# xbee_remote.net
KiCad netlist of a schematic drawn in EAGLE
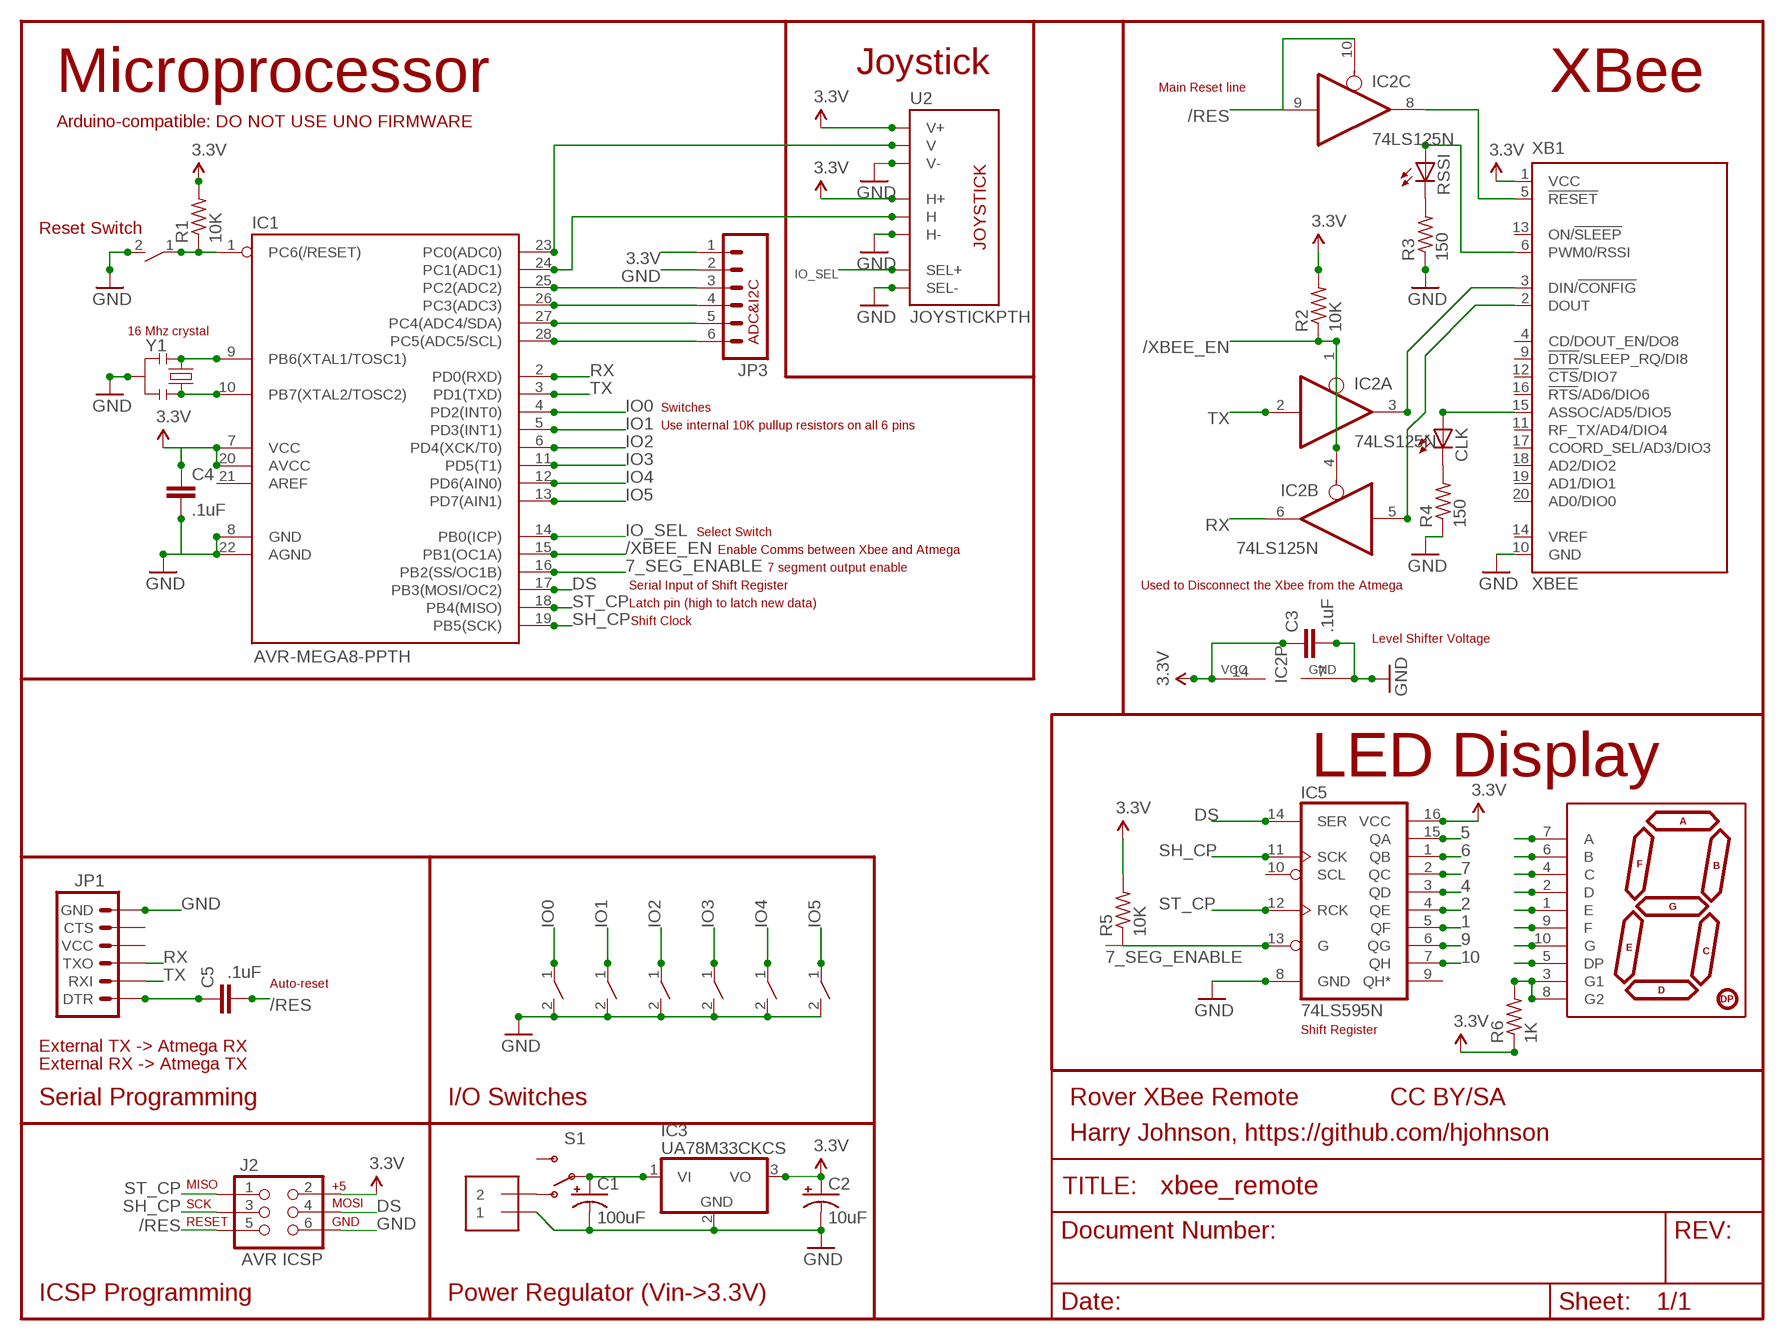
[diagram p0: schematic, sheet 1]

(export (version "E")
  (design (tool "Eeschema 10.0.6"))
  (components
    (comp (ref "C1")
      (value "100uF")
      (footprint "eagle-import:CPOL-RADIAL-100UF-25V")
      (libsource (lib "eagle-import") (part "CAP_POLPTH1"))
    )
    (comp (ref "C2")
      (value "10uF")
      (footprint "eagle-import:CPOL-RADIAL-10UF-25V")
      (libsource (lib "eagle-import") (part "CAP_POLPTH2"))
    )
    (comp (ref "C3")
      (value ".1uF")
      (footprint "eagle-import:CAP-PTH-SMALL2")
      (libsource (lib "eagle-import") (part "CAPPTH2"))
    )
    (comp (ref "C4")
      (value ".1uF")
      (footprint "eagle-import:CAP-PTH-SMALL2")
      (libsource (lib "eagle-import") (part "CAPPTH2"))
    )
    (comp (ref "C5")
      (value ".1uF")
      (footprint "eagle-import:CAP-PTH-SMALL2")
      (libsource (lib "eagle-import") (part "CAPPTH2"))
    )
    (comp (ref "CLK")
      (value "LED3MM")
      (footprint "eagle-import:LED3MM")
      (libsource (lib "eagle-import") (part "LED3MM"))
    )
    (comp (ref "IC1")
      (value "AVR-MEGA8-PPTH")
      (footprint "eagle-import:DIL28-3")
      (libsource (lib "eagle-import") (part "AVR-MEGA8-PPTH"))
    )
    (comp (ref "IC2")
      (value "74LS125N")
      (footprint "eagle-import:DIL14")
      (libsource (lib "eagle-import") (part "74125NLS"))
    )
    (comp (ref "IC3")
      (value "UA78M33CKCS")
      (footprint "eagle-import:TO220V")
      (libsource (lib "eagle-import") (part "78TV6"))
    )
    (comp (ref "IC5")
      (value "74LS595N")
      (footprint "eagle-import:DIL16")
      (libsource (lib "eagle-import") (part "74595NLS"))
    )
    (comp (ref "J1")
      (value "1X2-3.5MM")
      (footprint "eagle-import:3.5MMTERM")
      (libsource (lib "eagle-import") (part "1X2-3.5MM"))
    )
    (comp (ref "J2")
      (value "AVR ICSP")
      (footprint "eagle-import:2X3")
      (libsource (lib "eagle-import") (part "AVR_SPI_PRG_6PTH"))
    )
    (comp (ref "JP1")
      (value "ARDUINO_SERIAL_PROGRAMPTH")
      (footprint "eagle-import:1X06")
      (libsource (lib "eagle-import") (part "ARDUINO_SERIAL_PROGRAMPTH"))
    )
    (comp (ref "JP3")
      (value "M06SIP")
      (footprint "eagle-import:1X06")
      (libsource (lib "eagle-import") (part "M06SIP"))
    )
    (comp (ref "R1")
      (value "10K")
      (footprint "eagle-import:0207_10")
      (libsource (lib "eagle-import") (part "R-US_0207/10"))
    )
    (comp (ref "R2")
      (value "10K")
      (footprint "eagle-import:0207_10")
      (libsource (lib "eagle-import") (part "R-US_0207/10"))
    )
    (comp (ref "R3")
      (value "150")
      (footprint "eagle-import:0207_10")
      (libsource (lib "eagle-import") (part "R-US_0207/10"))
    )
    (comp (ref "R4")
      (value "150")
      (footprint "eagle-import:0207_10")
      (libsource (lib "eagle-import") (part "R-US_0207/10"))
    )
    (comp (ref "R5")
      (value "10K")
      (footprint "eagle-import:0207_10")
      (libsource (lib "eagle-import") (part "R-US_0207/10"))
    )
    (comp (ref "R6")
      (value "1K")
      (footprint "eagle-import:0207_10")
      (libsource (lib "eagle-import") (part "R-US_0207/10"))
    )
    (comp (ref "RSSI")
      (value "LED3MM")
      (footprint "eagle-import:LED3MM")
      (libsource (lib "eagle-import") (part "LED3MM"))
    )
    (comp (ref "S1")
      (value "SWITCH-SPSTPTH")
      (footprint "eagle-import:SWITCH-SPDT")
      (libsource (lib "eagle-import") (part "SWITCH-SPSTPTH"))
    )
    (comp (ref "U$4")
      (value "7-SEGMENT-DISPLAY-1\"-RED")
      (footprint "eagle-import:7-SEGMENT-1_PTH")
      (libsource (lib "eagle-import") (part "7-SEGMENT-DISPLAY-1{dblquote}-RED"))
    )
    (comp (ref "U$8")
      (value "TACT_TL1107")
      (footprint "eagle-import:TACT_TL1107")
      (libsource (lib "eagle-import") (part "TACT_TL1107"))
    )
    (comp (ref "U$9")
      (value "TACT_TL1107")
      (footprint "eagle-import:TACT_TL1107")
      (libsource (lib "eagle-import") (part "TACT_TL1107"))
    )
    (comp (ref "U$10")
      (value "TACT_TL1107")
      (footprint "eagle-import:TACT_TL1107")
      (libsource (lib "eagle-import") (part "TACT_TL1107"))
    )
    (comp (ref "U$11")
      (value "TACT_TL1107")
      (footprint "eagle-import:TACT_TL1107")
      (libsource (lib "eagle-import") (part "TACT_TL1107"))
    )
    (comp (ref "U$12")
      (value "TACT_TL1107")
      (footprint "eagle-import:TACT_TL1107")
      (libsource (lib "eagle-import") (part "TACT_TL1107"))
    )
    (comp (ref "U$13")
      (value "TACT_TL1107")
      (footprint "eagle-import:TACT_TL1107")
      (libsource (lib "eagle-import") (part "TACT_TL1107"))
    )
    (comp (ref "U$14")
      (value "TACT_TL1107")
      (footprint "eagle-import:TACT_TL1107")
      (libsource (lib "eagle-import") (part "TACT_TL1107"))
    )
    (comp (ref "U2")
      (value "JOYSTICKPTH")
      (footprint "eagle-import:JOYSTICK")
      (libsource (lib "eagle-import") (part "JOYSTICKPTH"))
    )
    (comp (ref "XB1")
      (value "XBEE")
      (footprint "eagle-import:XBEE")
      (fields (field (name "MPN") "XBP24-Z7UIT-004"))
      (libsource (lib "eagle-import") (part "XBEE"))
    )
    (comp (ref "Y1")
      (value "RESONATORPTH")
      (footprint "eagle-import:RESONATOR-PTH")
      (libsource (lib "eagle-import") (part "RESONATORPTH"))
    )
  )
  (nets
    (net (code "1") (name "/1") (class "Default")
      (node (ref "IC5") (pin "5") (pinfunction "QF_5") (pintype "tri_state"))
      (node (ref "U$4") (pin "1") (pinfunction "E_1") (pintype "bidirectional"))
    )
    (net (code "2") (name "/2") (class "Default")
      (node (ref "IC5") (pin "4") (pinfunction "QE_4") (pintype "tri_state"))
      (node (ref "U$4") (pin "2") (pinfunction "D_2") (pintype "bidirectional"))
    )
    (net (code "3") (name "/4") (class "Default")
      (node (ref "IC5") (pin "3") (pinfunction "QD_3") (pintype "tri_state"))
      (node (ref "U$4") (pin "4") (pinfunction "C_4") (pintype "bidirectional"))
    )
    (net (code "4") (name "/5") (class "Default")
      (node (ref "IC5") (pin "15") (pinfunction "QA_15") (pintype "tri_state"))
      (node (ref "U$4") (pin "5") (pinfunction "DP_5") (pintype "bidirectional"))
    )
    (net (code "5") (name "/6") (class "Default")
      (node (ref "IC5") (pin "1") (pinfunction "QB_1") (pintype "tri_state"))
      (node (ref "U$4") (pin "6") (pinfunction "B_6") (pintype "bidirectional"))
    )
    (net (code "6") (name "/7") (class "Default")
      (node (ref "IC5") (pin "2") (pinfunction "QC_2") (pintype "tri_state"))
      (node (ref "U$4") (pin "7") (pinfunction "A_7") (pintype "bidirectional"))
    )
    (net (code "7") (name "/7_SEG_ENABLE") (class "Default")
      (node (ref "IC1") (pin "16") (pinfunction "PB2(SS/OC1B)_16") (pintype "bidirectional"))
      (node (ref "IC5") (pin "13") (pinfunction "G_13") (pintype "input"))
      (node (ref "R5") (pin "1") (pinfunction "1_1") (pintype "passive"))
    )
    (net (code "8") (name "/9") (class "Default")
      (node (ref "IC5") (pin "6") (pinfunction "QG_6") (pintype "tri_state"))
      (node (ref "U$4") (pin "9") (pinfunction "F_9") (pintype "bidirectional"))
    )
    (net (code "9") (name "/10") (class "Default")
      (node (ref "IC5") (pin "7") (pinfunction "QH_7") (pintype "tri_state"))
      (node (ref "U$4") (pin "10") (pinfunction "G_10") (pintype "bidirectional"))
    )
    (net (code "10") (name "/DS") (class "Default")
      (node (ref "IC1") (pin "17") (pinfunction "PB3(MOSI/OC2)_17") (pintype "bidirectional"))
      (node (ref "IC5") (pin "14") (pinfunction "SER_14") (pintype "input"))
      (node (ref "J2") (pin "4") (pinfunction "4_4") (pintype "passive"))
    )
    (net (code "11") (name "/IO0") (class "Default")
      (node (ref "IC1") (pin "4") (pinfunction "PD2(INT0)_4") (pintype "bidirectional"))
      (node (ref "U$9") (pin "1") (pinfunction "1_1") (pintype "bidirectional"))
    )
    (net (code "12") (name "/IO1") (class "Default")
      (node (ref "IC1") (pin "5") (pinfunction "PD3(INT1)_5") (pintype "bidirectional"))
      (node (ref "U$10") (pin "1") (pinfunction "1_1") (pintype "bidirectional"))
    )
    (net (code "13") (name "/IO2") (class "Default")
      (node (ref "IC1") (pin "6") (pinfunction "PD4(XCK/T0)_6") (pintype "bidirectional"))
      (node (ref "U$11") (pin "1") (pinfunction "1_1") (pintype "bidirectional"))
    )
    (net (code "14") (name "/IO3") (class "Default")
      (node (ref "IC1") (pin "11") (pinfunction "PD5(T1)_11") (pintype "bidirectional"))
      (node (ref "U$12") (pin "1") (pinfunction "1_1") (pintype "bidirectional"))
    )
    (net (code "15") (name "/IO4") (class "Default")
      (node (ref "IC1") (pin "12") (pinfunction "PD6(AIN0)_12") (pintype "bidirectional"))
      (node (ref "U$13") (pin "1") (pinfunction "1_1") (pintype "bidirectional"))
    )
    (net (code "16") (name "/IO5") (class "Default")
      (node (ref "IC1") (pin "13") (pinfunction "PD7(AIN1)_13") (pintype "bidirectional"))
      (node (ref "U$14") (pin "1") (pinfunction "1_1") (pintype "bidirectional"))
    )
    (net (code "17") (name "/IO_SEL") (class "Default")
      (node (ref "IC1") (pin "14") (pinfunction "PB0(ICP)_14") (pintype "bidirectional"))
      (node (ref "U2") (pin "B1A") (pinfunction "SEL+_B1A") (pintype "bidirectional"))
    )
    (net (code "18") (name "/RX") (class "Default")
      (node (ref "IC1") (pin "2") (pinfunction "PD0(RXD)_2") (pintype "bidirectional"))
      (node (ref "IC2") (pin "6") (pinfunction "O_6") (pintype "tri_state"))
      (node (ref "JP1") (pin "3") (pinfunction "TXO_3") (pintype "passive"))
    )
    (net (code "19") (name "/SH_CP") (class "Default")
      (node (ref "IC1") (pin "19") (pinfunction "PB5(SCK)_19") (pintype "bidirectional"))
      (node (ref "IC5") (pin "11") (pinfunction "SCK_11") (pintype "input"))
      (node (ref "J2") (pin "3") (pinfunction "3_3") (pintype "passive"))
    )
    (net (code "20") (name "/ST_CP") (class "Default")
      (node (ref "IC1") (pin "18") (pinfunction "PB4(MISO)_18") (pintype "bidirectional"))
      (node (ref "IC5") (pin "12") (pinfunction "RCK_12") (pintype "input"))
      (node (ref "J2") (pin "1") (pinfunction "1_1") (pintype "passive"))
    )
    (net (code "21") (name "/TX") (class "Default")
      (node (ref "IC1") (pin "3") (pinfunction "PD1(TXD)_3") (pintype "bidirectional"))
      (node (ref "IC2") (pin "2") (pinfunction "I_2") (pintype "input"))
      (node (ref "JP1") (pin "2") (pinfunction "RXI_2") (pintype "passive"))
    )
    (net (code "22") (name "/{slash}RES") (class "Default")
      (node (ref "C5") (pin "2") (pinfunction "2_2") (pintype "passive"))
      (node (ref "IC1") (pin "1") (pinfunction "PC6(/RESET)_1") (pintype "bidirectional"))
      (node (ref "IC2") (pin "10") (pinfunction "OE_10") (pintype "input"))
      (node (ref "IC2") (pin "9") (pinfunction "I_9") (pintype "input"))
      (node (ref "J2") (pin "5") (pinfunction "5_5") (pintype "passive"))
      (node (ref "R1") (pin "1") (pinfunction "1_1") (pintype "passive"))
      (node (ref "U$8") (pin "1") (pinfunction "1_1") (pintype "bidirectional"))
    )
    (net (code "23") (name "/{slash}XBEE_EN") (class "Default")
      (node (ref "IC1") (pin "15") (pinfunction "PB1(OC1A)_15") (pintype "bidirectional"))
      (node (ref "IC2") (pin "1") (pinfunction "OE_1") (pintype "input"))
      (node (ref "IC2") (pin "4") (pinfunction "OE_4") (pintype "input"))
      (node (ref "R2") (pin "1") (pinfunction "1_1") (pintype "passive"))
    )
    (net (code "24") (name "3.3V") (class "Default")
      (node (ref "C2") (pin "1") (pinfunction "+_1") (pintype "passive"))
      (node (ref "C3") (pin "1") (pinfunction "1_1") (pintype "passive"))
      (node (ref "C4") (pin "1") (pinfunction "1_1") (pintype "passive"))
      (node (ref "IC1") (pin "20") (pinfunction "AVCC_20") (pintype "bidirectional"))
      (node (ref "IC1") (pin "7") (pinfunction "VCC_7") (pintype "bidirectional"))
      (node (ref "IC2") (pin "14") (pinfunction "VCC_14") (pintype "power_in"))
      (node (ref "IC3") (pin "3") (pinfunction "VO_3") (pintype "passive"))
      (node (ref "IC5") (pin "16") (pinfunction "VCC_16") (pintype "power_in"))
      (node (ref "J2") (pin "2") (pinfunction "2_2") (pintype "passive"))
      (node (ref "JP3") (pin "1") (pinfunction "1_1") (pintype "passive"))
      (node (ref "R1") (pin "2") (pinfunction "2_2") (pintype "passive"))
      (node (ref "R2") (pin "2") (pinfunction "2_2") (pintype "passive"))
      (node (ref "R5") (pin "2") (pinfunction "2_2") (pintype "passive"))
      (node (ref "R6") (pin "1") (pinfunction "1_1") (pintype "passive"))
      (node (ref "U2") (pin "H1") (pinfunction "H+_H1") (pintype "bidirectional"))
      (node (ref "U2") (pin "V1") (pinfunction "V+_V1") (pintype "bidirectional"))
      (node (ref "XB1") (pin "1") (pinfunction "VCC_1") (pintype "power_in"))
    )
    (net (code "25") (name "GND") (class "Default")
      (node (ref "C1") (pin "2") (pinfunction "-_2") (pintype "passive"))
      (node (ref "C2") (pin "2") (pinfunction "-_2") (pintype "passive"))
      (node (ref "C3") (pin "2") (pinfunction "2_2") (pintype "passive"))
      (node (ref "C4") (pin "2") (pinfunction "2_2") (pintype "passive"))
      (node (ref "IC1") (pin "22") (pinfunction "AGND_22") (pintype "bidirectional"))
      (node (ref "IC1") (pin "8") (pinfunction "GND_8") (pintype "bidirectional"))
      (node (ref "IC2") (pin "7") (pinfunction "GND_7") (pintype "power_in"))
      (node (ref "IC3") (pin "2") (pinfunction "GND_2") (pintype "passive"))
      (node (ref "IC5") (pin "8") (pinfunction "GND_8") (pintype "power_in"))
      (node (ref "J1") (pin "1") (pinfunction "1_1") (pintype "passive"))
      (node (ref "J2") (pin "6") (pinfunction "6_6") (pintype "passive"))
      (node (ref "JP1") (pin "6") (pinfunction "GND_6") (pintype "passive"))
      (node (ref "JP3") (pin "2") (pinfunction "2_2") (pintype "passive"))
      (node (ref "R3") (pin "1") (pinfunction "1_1") (pintype "passive"))
      (node (ref "R4") (pin "1") (pinfunction "1_1") (pintype "passive"))
      (node (ref "U$10") (pin "2") (pinfunction "2_2") (pintype "bidirectional"))
      (node (ref "U$11") (pin "2") (pinfunction "2_2") (pintype "bidirectional"))
      (node (ref "U$12") (pin "2") (pinfunction "2_2") (pintype "bidirectional"))
      (node (ref "U$13") (pin "2") (pinfunction "2_2") (pintype "bidirectional"))
      (node (ref "U$14") (pin "2") (pinfunction "2_2") (pintype "bidirectional"))
      (node (ref "U$8") (pin "2") (pinfunction "2_2") (pintype "bidirectional"))
      (node (ref "U$9") (pin "2") (pinfunction "2_2") (pintype "bidirectional"))
      (node (ref "U2") (pin "B2A") (pinfunction "SEL-_B2A") (pintype "bidirectional"))
      (node (ref "U2") (pin "H3") (pinfunction "H-_H3") (pintype "bidirectional"))
      (node (ref "U2") (pin "V3") (pinfunction "V-_V3") (pintype "bidirectional"))
      (node (ref "XB1") (pin "10") (pinfunction "GND_10") (pintype "power_in"))
      (node (ref "Y1") (pin "2") (pinfunction "2_2") (pintype "passive"))
    )
    (net (code "26") (name "Net-(C1-+)") (class "Default")
      (node (ref "C1") (pin "1") (pinfunction "+_1") (pintype "passive"))
      (node (ref "IC3") (pin "1") (pinfunction "VI_1") (pintype "input"))
      (node (ref "S1") (pin "2") (pinfunction "P_2") (pintype "passive"))
    )
    (net (code "27") (name "Net-(CLK-C)") (class "Default")
      (node (ref "CLK") (pin "K") (pinfunction "C_K") (pintype "passive"))
      (node (ref "R4") (pin "2") (pinfunction "2_2") (pintype "passive"))
    )
    (net (code "28") (name "Net-(IC1-PB6(XTAL1{slash}TOSC1))") (class "Default")
      (node (ref "IC1") (pin "9") (pinfunction "PB6(XTAL1/TOSC1)_9") (pintype "bidirectional"))
      (node (ref "Y1") (pin "1") (pinfunction "1_1") (pintype "passive"))
    )
    (net (code "29") (name "Net-(IC1-PB7(XTAL2{slash}TOSC2))") (class "Default")
      (node (ref "IC1") (pin "10") (pinfunction "PB7(XTAL2/TOSC2)_10") (pintype "bidirectional"))
      (node (ref "Y1") (pin "3") (pinfunction "3_3") (pintype "passive"))
    )
    (net (code "30") (name "Net-(IC1-PC0(ADC0))") (class "Default")
      (node (ref "IC1") (pin "23") (pinfunction "PC0(ADC0)_23") (pintype "bidirectional"))
      (node (ref "U2") (pin "V2") (pinfunction "V_V2") (pintype "bidirectional"))
    )
    (net (code "31") (name "Net-(IC1-PC1(ADC1))") (class "Default")
      (node (ref "IC1") (pin "24") (pinfunction "PC1(ADC1)_24") (pintype "bidirectional"))
      (node (ref "U2") (pin "H2") (pinfunction "H_H2") (pintype "bidirectional"))
    )
    (net (code "32") (name "Net-(IC1-PC2(ADC2))") (class "Default")
      (node (ref "IC1") (pin "25") (pinfunction "PC2(ADC2)_25") (pintype "bidirectional"))
      (node (ref "JP3") (pin "3") (pinfunction "3_3") (pintype "passive"))
    )
    (net (code "33") (name "Net-(IC1-PC3(ADC3))") (class "Default")
      (node (ref "IC1") (pin "26") (pinfunction "PC3(ADC3)_26") (pintype "bidirectional"))
      (node (ref "JP3") (pin "4") (pinfunction "4_4") (pintype "passive"))
    )
    (net (code "34") (name "Net-(IC1-PC4(ADC4{slash}SDA))") (class "Default")
      (node (ref "IC1") (pin "27") (pinfunction "PC4(ADC4/SDA)_27") (pintype "bidirectional"))
      (node (ref "JP3") (pin "5") (pinfunction "5_5") (pintype "passive"))
    )
    (net (code "35") (name "Net-(IC1-PC5(ADC5{slash}SCL))") (class "Default")
      (node (ref "IC1") (pin "28") (pinfunction "PC5(ADC5/SCL)_28") (pintype "bidirectional"))
      (node (ref "JP3") (pin "6") (pinfunction "6_6") (pintype "passive"))
    )
    (net (code "36") (name "Net-(IC2A-O)") (class "Default")
      (node (ref "IC2") (pin "3") (pinfunction "O_3") (pintype "tri_state"))
      (node (ref "XB1") (pin "3") (pinfunction "DIN/~{CONFIG}_3") (pintype "input"))
    )
    (net (code "37") (name "Net-(IC2B-I)") (class "Default")
      (node (ref "IC2") (pin "5") (pinfunction "I_5") (pintype "input"))
      (node (ref "XB1") (pin "2") (pinfunction "DOUT_2") (pintype "output"))
    )
    (net (code "38") (name "Net-(IC2C-O)") (class "Default")
      (node (ref "IC2") (pin "8") (pinfunction "O_8") (pintype "tri_state"))
      (node (ref "XB1") (pin "5") (pinfunction "~{RESET}_5") (pintype "input"))
    )
    (net (code "39") (name "Net-(JP1-DTR)") (class "Default")
      (node (ref "C5") (pin "1") (pinfunction "1_1") (pintype "passive"))
      (node (ref "JP1") (pin "1") (pinfunction "DTR_1") (pintype "passive"))
    )
    (net (code "40") (name "Net-(RSSI-C)") (class "Default")
      (node (ref "R3") (pin "2") (pinfunction "2_2") (pintype "passive"))
      (node (ref "RSSI") (pin "K") (pinfunction "C_K") (pintype "passive"))
    )
    (net (code "41") (name "Net-(S1-O)") (class "Default")
      (node (ref "J1") (pin "2") (pinfunction "2_2") (pintype "passive"))
      (node (ref "S1") (pin "1") (pinfunction "O_1") (pintype "passive"))
    )
    (net (code "42") (name "Net-(U$4-G1)") (class "Default")
      (node (ref "R6") (pin "2") (pinfunction "2_2") (pintype "passive"))
      (node (ref "U$4") (pin "3") (pinfunction "G1_3") (pintype "bidirectional"))
      (node (ref "U$4") (pin "8") (pinfunction "G2_8") (pintype "bidirectional"))
    )
    (net (code "43") (name "Net-(XB1-ASSOC{slash}AD5{slash}DIO5)") (class "Default")
      (node (ref "CLK") (pin "A") (pinfunction "A_A") (pintype "passive"))
      (node (ref "XB1") (pin "15") (pinfunction "ASSOC/AD5/DIO5_15") (pintype "bidirectional"))
    )
    (net (code "44") (name "Net-(XB1-PWM0{slash}RSSI)") (class "Default")
      (node (ref "RSSI") (pin "A") (pinfunction "A_A") (pintype "passive"))
      (node (ref "XB1") (pin "6") (pinfunction "PWM0/RSSI_6") (pintype "output"))
    )
    (net (code "45") (name "unconnected-(IC1-AREF-Pad21)") (class "Default")
      (node (ref "IC1") (pin "21") (pinfunction "AREF_21") (pintype "bidirectional"))
    )
    (net (code "46") (name "unconnected-(IC5-QH*-Pad9)") (class "Default")
      (node (ref "IC5") (pin "9") (pinfunction "QH*_9") (pintype "tri_state"))
    )
    (net (code "47") (name "unconnected-(IC5-SCL-Pad10)") (class "Default")
      (node (ref "IC5") (pin "10") (pinfunction "SCL_10") (pintype "input"))
    )
    (net (code "48") (name "unconnected-(JP1-CTS-Pad5)") (class "Default")
      (node (ref "JP1") (pin "5") (pinfunction "CTS_5") (pintype "passive"))
    )
    (net (code "49") (name "unconnected-(JP1-VCC-Pad4)") (class "Default")
      (node (ref "JP1") (pin "4") (pinfunction "VCC_4") (pintype "passive"))
    )
    (net (code "50") (name "unconnected-(S1-S-Pad3)") (class "Default")
      (node (ref "S1") (pin "3") (pinfunction "S_3") (pintype "passive"))
    )
    (net (code "51") (name "unconnected-(XB1-AD0{slash}DIO0-Pad20)") (class "Default")
      (node (ref "XB1") (pin "20") (pinfunction "AD0/DIO0_20") (pintype "bidirectional"))
    )
    (net (code "52") (name "unconnected-(XB1-AD1{slash}DIO1-Pad19)") (class "Default")
      (node (ref "XB1") (pin "19") (pinfunction "AD1/DIO1_19") (pintype "bidirectional"))
    )
    (net (code "53") (name "unconnected-(XB1-AD2{slash}DIO2-Pad18)") (class "Default")
      (node (ref "XB1") (pin "18") (pinfunction "AD2/DIO2_18") (pintype "bidirectional"))
    )
    (net (code "54") (name "unconnected-(XB1-CD{slash}DOUT_EN{slash}DO8-Pad4)") (class "Default")
      (node (ref "XB1") (pin "4") (pinfunction "CD/DOUT_EN/DO8_4") (pintype "output"))
    )
    (net (code "55") (name "unconnected-(XB1-COORD_SEL{slash}AD3{slash}DIO3-Pad17)") (class "Default")
      (node (ref "XB1") (pin "17") (pinfunction "COORD_SEL/AD3/DIO3_17") (pintype "bidirectional"))
    )
    (net (code "56") (name "unconnected-(XB1-ON{slash}~{SLEEP}-Pad13)") (class "Default")
      (node (ref "XB1") (pin "13") (pinfunction "ON/~{SLEEP}_13") (pintype "output"))
    )
    (net (code "57") (name "unconnected-(XB1-RF_TX{slash}AD4{slash}DIO4-Pad11)") (class "Default")
      (node (ref "XB1") (pin "11") (pinfunction "RF_TX/AD4/DIO4_11") (pintype "bidirectional"))
    )
    (net (code "58") (name "unconnected-(XB1-VREF-Pad14)") (class "Default")
      (node (ref "XB1") (pin "14") (pinfunction "VREF_14") (pintype "input"))
    )
    (net (code "59") (name "unconnected-(XB1-~{CTS}{slash}DIO7-Pad12)") (class "Default")
      (node (ref "XB1") (pin "12") (pinfunction "~{CTS}/DIO7_12") (pintype "bidirectional"))
    )
    (net (code "60") (name "unconnected-(XB1-~{DTR}{slash}SLEEP_RQ{slash}DI8-Pad9)") (class "Default")
      (node (ref "XB1") (pin "9") (pinfunction "~{DTR}/SLEEP_RQ/DI8_9") (pintype "bidirectional"))
    )
    (net (code "61") (name "unconnected-(XB1-~{RTS}{slash}AD6{slash}DIO6-Pad16)") (class "Default")
      (node (ref "XB1") (pin "16") (pinfunction "~{RTS}/AD6/DIO6_16") (pintype "bidirectional"))
    )
  )
)
